# Multiboard_Analog_Connector.net
KiCad netlist of a schematic drawn in Altium Designer
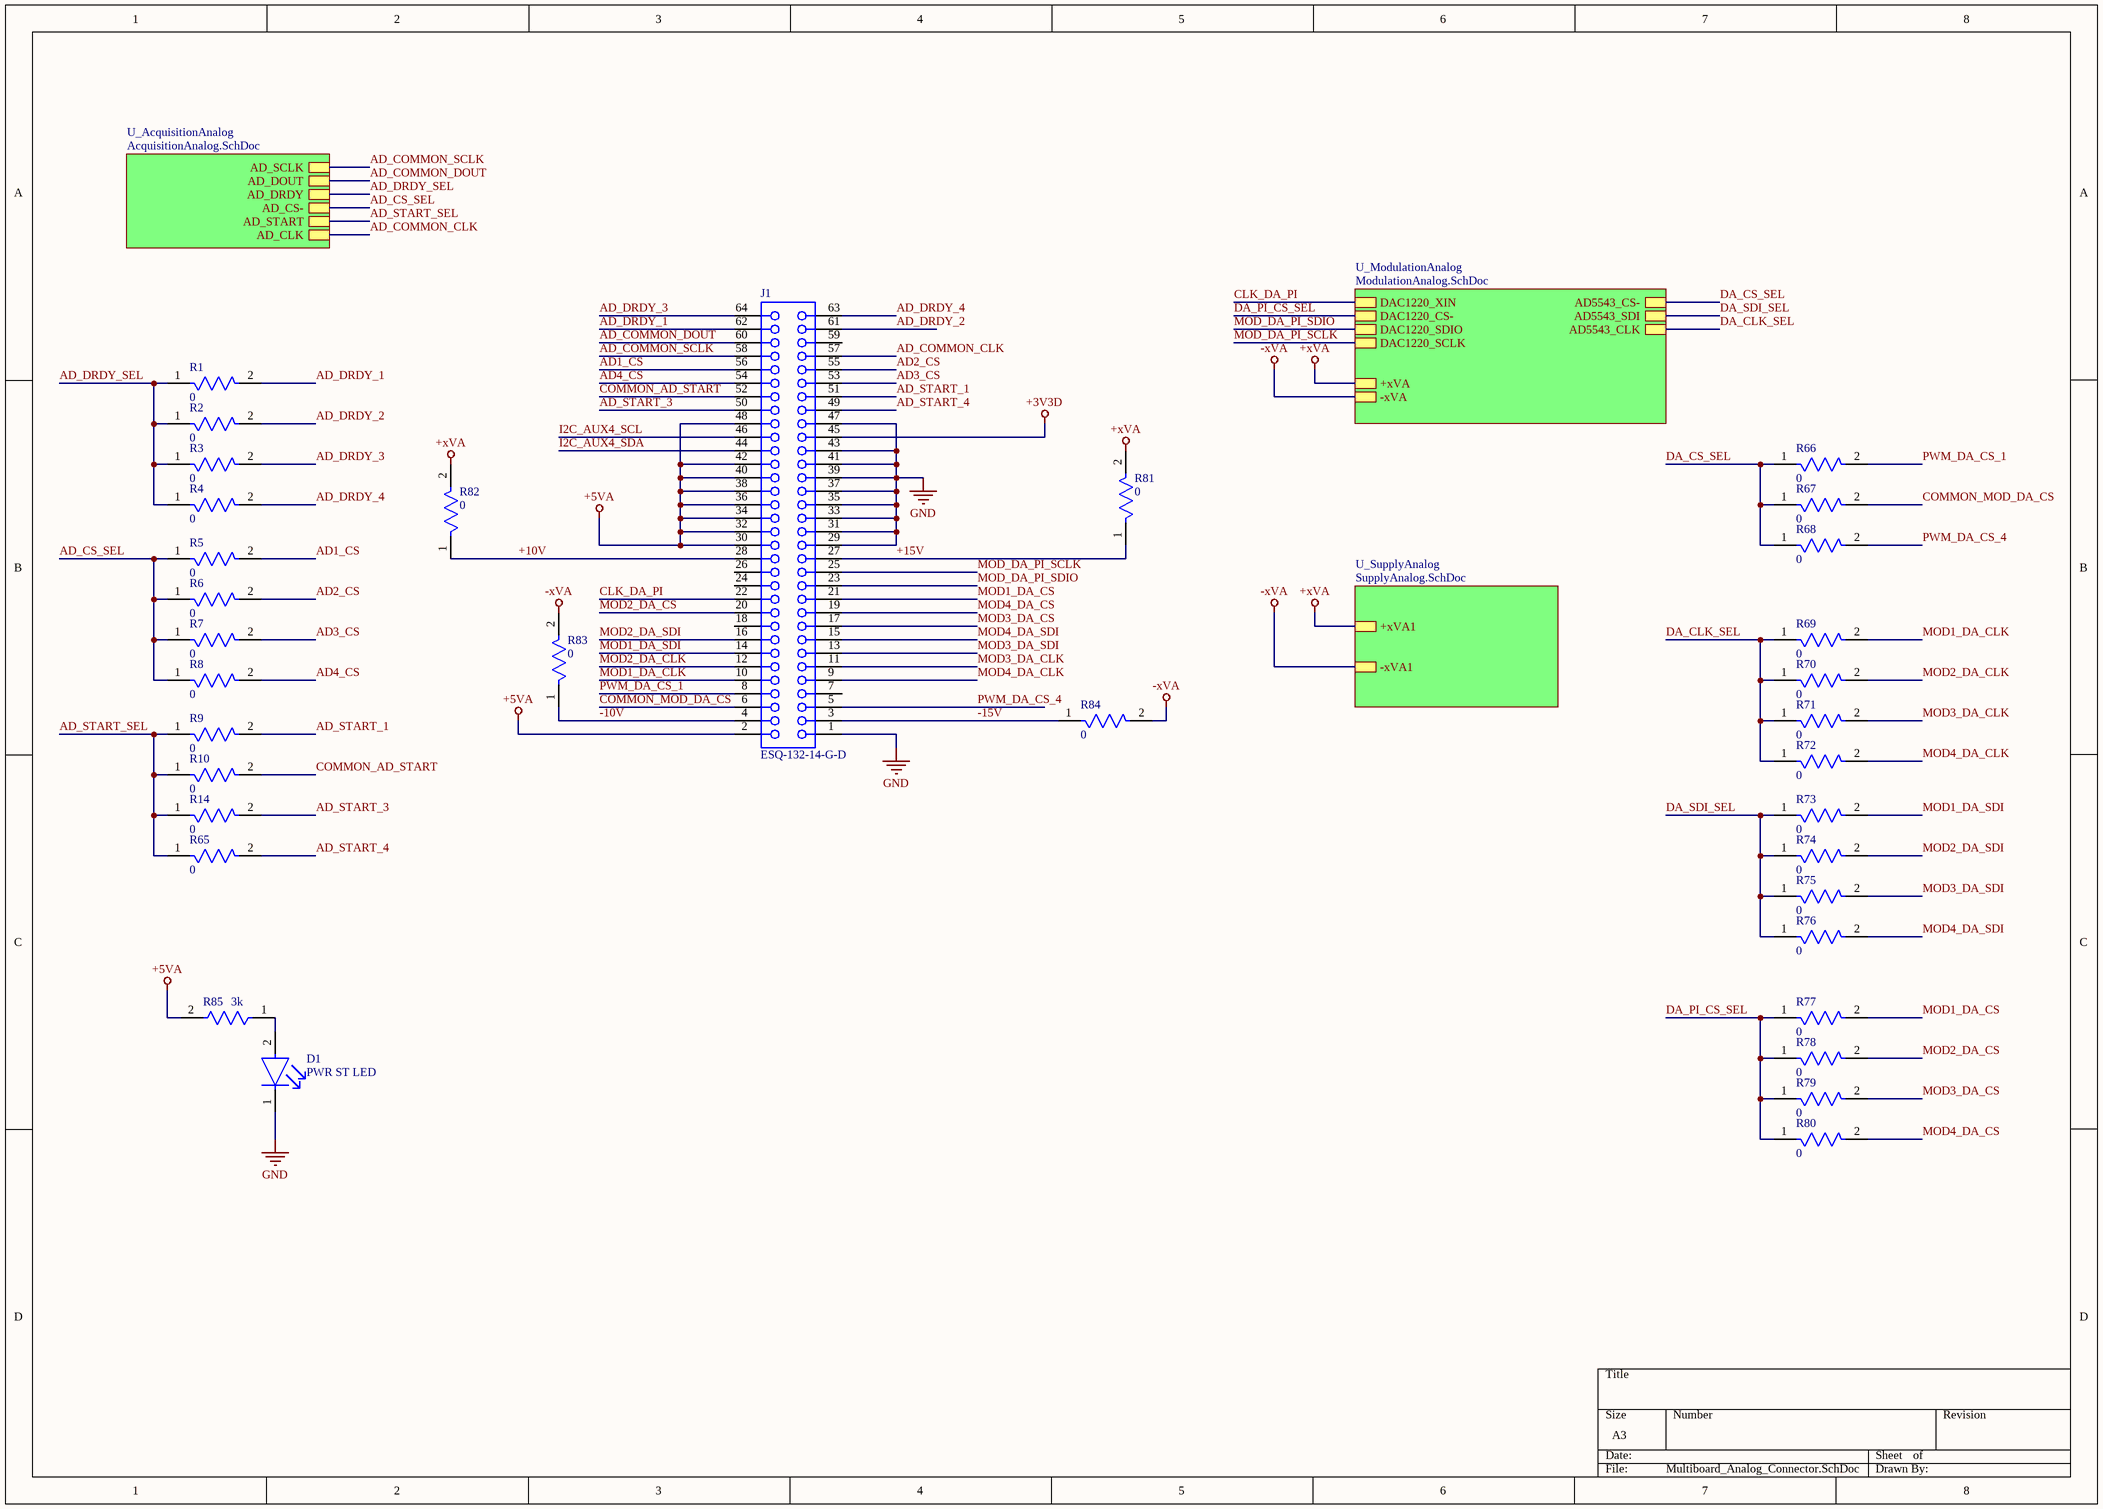
[diagram p0: Multiboard_Analog_Connector.SchDoc]

(export (version "E")
  (design (tool "Eeschema 10.0.6"))
  (components
    (comp (ref "D1")
      (value "PWR ST LED")
      (footprint "FP-APHCM2012SYCK-F01-MFG")
      (description "LED YELLOW CLEAR CHIP SMD")
      (libsource (lib "Altium Content Vault") (part "8706943c75ba83719d021d2fdc84c58"))
    )
    (comp (ref "J1")
      (value "ESQ-132-14-G-D")
      (footprint "SMTC-ESQ-132-14-X-D")
      (fields (field (name "MANUFACTURER") "Samtec"))
      (libsource (lib "Altium Content Vault") (part "SMTC-ESQ-132-14-X-D"))
    )
    (comp (ref "R1")
      (value "0")
      (footprint "FP-RR1220-MFG")
      (description "49.9Ω ±0.5% 0.1W 1/10W Chip Resistor 0805 (2012 Metric) Thin Film")
      (fields (field (name "TOLERANCE") "0.5%"))
      (libsource (lib "Altium Content Vault") (part "1029c3af85768c4190bb7ad29bc67b5"))
    )
    (comp (ref "R2")
      (value "0")
      (footprint "FP-RR1220-MFG")
      (description "49.9Ω ±0.5% 0.1W 1/10W Chip Resistor 0805 (2012 Metric) Thin Film")
      (fields (field (name "TOLERANCE") "0.5%"))
      (libsource (lib "Altium Content Vault") (part "1029c3af85768c4190bb7ad29bc67b5"))
    )
    (comp (ref "R3")
      (value "0")
      (footprint "FP-RR1220-MFG")
      (description "49.9Ω ±0.5% 0.1W 1/10W Chip Resistor 0805 (2012 Metric) Thin Film")
      (fields (field (name "TOLERANCE") "0.5%"))
      (libsource (lib "Altium Content Vault") (part "1029c3af85768c4190bb7ad29bc67b5"))
    )
    (comp (ref "R4")
      (value "0")
      (footprint "FP-RR1220-MFG")
      (description "49.9Ω ±0.5% 0.1W 1/10W Chip Resistor 0805 (2012 Metric) Thin Film")
      (fields (field (name "TOLERANCE") "0.5%"))
      (libsource (lib "Altium Content Vault") (part "1029c3af85768c4190bb7ad29bc67b5"))
    )
    (comp (ref "R5")
      (value "0")
      (footprint "FP-RR1220-MFG")
      (description "49.9Ω ±0.5% 0.1W 1/10W Chip Resistor 0805 (2012 Metric) Thin Film")
      (fields (field (name "TOLERANCE") "0.5%"))
      (libsource (lib "Altium Content Vault") (part "1029c3af85768c4190bb7ad29bc67b5"))
    )
    (comp (ref "R6")
      (value "0")
      (footprint "FP-RR1220-MFG")
      (description "49.9Ω ±0.5% 0.1W 1/10W Chip Resistor 0805 (2012 Metric) Thin Film")
      (fields (field (name "TOLERANCE") "0.5%"))
      (libsource (lib "Altium Content Vault") (part "1029c3af85768c4190bb7ad29bc67b5"))
    )
    (comp (ref "R7")
      (value "0")
      (footprint "FP-RR1220-MFG")
      (description "49.9Ω ±0.5% 0.1W 1/10W Chip Resistor 0805 (2012 Metric) Thin Film")
      (fields (field (name "TOLERANCE") "0.5%"))
      (libsource (lib "Altium Content Vault") (part "1029c3af85768c4190bb7ad29bc67b5"))
    )
    (comp (ref "R8")
      (value "0")
      (footprint "FP-RR1220-MFG")
      (description "49.9Ω ±0.5% 0.1W 1/10W Chip Resistor 0805 (2012 Metric) Thin Film")
      (fields (field (name "TOLERANCE") "0.5%"))
      (libsource (lib "Altium Content Vault") (part "1029c3af85768c4190bb7ad29bc67b5"))
    )
    (comp (ref "R9")
      (value "0")
      (footprint "FP-RR1220-MFG")
      (description "49.9Ω ±0.5% 0.1W 1/10W Chip Resistor 0805 (2012 Metric) Thin Film")
      (fields (field (name "TOLERANCE") "0.5%"))
      (libsource (lib "Altium Content Vault") (part "1029c3af85768c4190bb7ad29bc67b5"))
    )
    (comp (ref "R10")
      (value "0")
      (footprint "FP-RR1220-MFG")
      (description "49.9Ω ±0.5% 0.1W 1/10W Chip Resistor 0805 (2012 Metric) Thin Film")
      (fields (field (name "TOLERANCE") "0.5%"))
      (libsource (lib "Altium Content Vault") (part "1029c3af85768c4190bb7ad29bc67b5"))
    )
    (comp (ref "R14")
      (value "0")
      (footprint "FP-RR1220-MFG")
      (description "49.9Ω ±0.5% 0.1W 1/10W Chip Resistor 0805 (2012 Metric) Thin Film")
      (fields (field (name "TOLERANCE") "0.5%"))
      (libsource (lib "Altium Content Vault") (part "1029c3af85768c4190bb7ad29bc67b5"))
    )
    (comp (ref "R65")
      (value "0")
      (footprint "FP-RR1220-MFG")
      (description "49.9Ω ±0.5% 0.1W 1/10W Chip Resistor 0805 (2012 Metric) Thin Film")
      (fields (field (name "TOLERANCE") "0.5%"))
      (libsource (lib "Altium Content Vault") (part "1029c3af85768c4190bb7ad29bc67b5"))
    )
    (comp (ref "R66")
      (value "0")
      (footprint "FP-RR1220-MFG")
      (description "49.9Ω ±0.5% 0.1W 1/10W Chip Resistor 0805 (2012 Metric) Thin Film")
      (fields (field (name "TOLERANCE") "0.5%"))
      (libsource (lib "Altium Content Vault") (part "1029c3af85768c4190bb7ad29bc67b5"))
    )
    (comp (ref "R67")
      (value "0")
      (footprint "FP-RR1220-MFG")
      (description "49.9Ω ±0.5% 0.1W 1/10W Chip Resistor 0805 (2012 Metric) Thin Film")
      (fields (field (name "TOLERANCE") "0.5%"))
      (libsource (lib "Altium Content Vault") (part "1029c3af85768c4190bb7ad29bc67b5"))
    )
    (comp (ref "R68")
      (value "0")
      (footprint "FP-RR1220-MFG")
      (description "49.9Ω ±0.5% 0.1W 1/10W Chip Resistor 0805 (2012 Metric) Thin Film")
      (fields (field (name "TOLERANCE") "0.5%"))
      (libsource (lib "Altium Content Vault") (part "1029c3af85768c4190bb7ad29bc67b5"))
    )
    (comp (ref "R69")
      (value "0")
      (footprint "FP-RR1220-MFG")
      (description "49.9Ω ±0.5% 0.1W 1/10W Chip Resistor 0805 (2012 Metric) Thin Film")
      (fields (field (name "TOLERANCE") "0.5%"))
      (libsource (lib "Altium Content Vault") (part "1029c3af85768c4190bb7ad29bc67b5"))
    )
    (comp (ref "R70")
      (value "0")
      (footprint "FP-RR1220-MFG")
      (description "49.9Ω ±0.5% 0.1W 1/10W Chip Resistor 0805 (2012 Metric) Thin Film")
      (fields (field (name "TOLERANCE") "0.5%"))
      (libsource (lib "Altium Content Vault") (part "1029c3af85768c4190bb7ad29bc67b5"))
    )
    (comp (ref "R71")
      (value "0")
      (footprint "FP-RR1220-MFG")
      (description "49.9Ω ±0.5% 0.1W 1/10W Chip Resistor 0805 (2012 Metric) Thin Film")
      (fields (field (name "TOLERANCE") "0.5%"))
      (libsource (lib "Altium Content Vault") (part "1029c3af85768c4190bb7ad29bc67b5"))
    )
    (comp (ref "R72")
      (value "0")
      (footprint "FP-RR1220-MFG")
      (description "49.9Ω ±0.5% 0.1W 1/10W Chip Resistor 0805 (2012 Metric) Thin Film")
      (fields (field (name "TOLERANCE") "0.5%"))
      (libsource (lib "Altium Content Vault") (part "1029c3af85768c4190bb7ad29bc67b5"))
    )
    (comp (ref "R73")
      (value "0")
      (footprint "FP-RR1220-MFG")
      (description "49.9Ω ±0.5% 0.1W 1/10W Chip Resistor 0805 (2012 Metric) Thin Film")
      (fields (field (name "TOLERANCE") "0.5%"))
      (libsource (lib "Altium Content Vault") (part "1029c3af85768c4190bb7ad29bc67b5"))
    )
    (comp (ref "R74")
      (value "0")
      (footprint "FP-RR1220-MFG")
      (description "49.9Ω ±0.5% 0.1W 1/10W Chip Resistor 0805 (2012 Metric) Thin Film")
      (fields (field (name "TOLERANCE") "0.5%"))
      (libsource (lib "Altium Content Vault") (part "1029c3af85768c4190bb7ad29bc67b5"))
    )
    (comp (ref "R75")
      (value "0")
      (footprint "FP-RR1220-MFG")
      (description "49.9Ω ±0.5% 0.1W 1/10W Chip Resistor 0805 (2012 Metric) Thin Film")
      (fields (field (name "TOLERANCE") "0.5%"))
      (libsource (lib "Altium Content Vault") (part "1029c3af85768c4190bb7ad29bc67b5"))
    )
    (comp (ref "R76")
      (value "0")
      (footprint "FP-RR1220-MFG")
      (description "49.9Ω ±0.5% 0.1W 1/10W Chip Resistor 0805 (2012 Metric) Thin Film")
      (fields (field (name "TOLERANCE") "0.5%"))
      (libsource (lib "Altium Content Vault") (part "1029c3af85768c4190bb7ad29bc67b5"))
    )
    (comp (ref "R77")
      (value "0")
      (footprint "FP-RR1220-MFG")
      (description "49.9Ω ±0.5% 0.1W 1/10W Chip Resistor 0805 (2012 Metric) Thin Film")
      (fields (field (name "TOLERANCE") "0.5%"))
      (libsource (lib "Altium Content Vault") (part "1029c3af85768c4190bb7ad29bc67b5"))
    )
    (comp (ref "R78")
      (value "0")
      (footprint "FP-RR1220-MFG")
      (description "49.9Ω ±0.5% 0.1W 1/10W Chip Resistor 0805 (2012 Metric) Thin Film")
      (fields (field (name "TOLERANCE") "0.5%"))
      (libsource (lib "Altium Content Vault") (part "1029c3af85768c4190bb7ad29bc67b5"))
    )
    (comp (ref "R79")
      (value "0")
      (footprint "FP-RR1220-MFG")
      (description "49.9Ω ±0.5% 0.1W 1/10W Chip Resistor 0805 (2012 Metric) Thin Film")
      (fields (field (name "TOLERANCE") "0.5%"))
      (libsource (lib "Altium Content Vault") (part "1029c3af85768c4190bb7ad29bc67b5"))
    )
    (comp (ref "R80")
      (value "0")
      (footprint "FP-RR1220-MFG")
      (description "49.9Ω ±0.5% 0.1W 1/10W Chip Resistor 0805 (2012 Metric) Thin Film")
      (fields (field (name "TOLERANCE") "0.5%"))
      (libsource (lib "Altium Content Vault") (part "1029c3af85768c4190bb7ad29bc67b5"))
    )
    (comp (ref "R81")
      (value "0")
      (footprint "FP-RR1220-MFG")
      (description "49.9Ω ±0.5% 0.1W 1/10W Chip Resistor 0805 (2012 Metric) Thin Film")
      (fields (field (name "TOLERANCE") "0.5%"))
      (libsource (lib "Altium Content Vault") (part "1029c3af85768c4190bb7ad29bc67b5"))
    )
    (comp (ref "R82")
      (value "0")
      (footprint "FP-RR1220-MFG")
      (description "49.9Ω ±0.5% 0.1W 1/10W Chip Resistor 0805 (2012 Metric) Thin Film")
      (fields (field (name "TOLERANCE") "0.5%"))
      (libsource (lib "Altium Content Vault") (part "1029c3af85768c4190bb7ad29bc67b5"))
    )
    (comp (ref "R83")
      (value "0")
      (footprint "FP-RR1220-MFG")
      (description "49.9Ω ±0.5% 0.1W 1/10W Chip Resistor 0805 (2012 Metric) Thin Film")
      (fields (field (name "TOLERANCE") "0.5%"))
      (libsource (lib "Altium Content Vault") (part "1029c3af85768c4190bb7ad29bc67b5"))
    )
    (comp (ref "R84")
      (value "0")
      (footprint "FP-RR1220-MFG")
      (description "49.9Ω ±0.5% 0.1W 1/10W Chip Resistor 0805 (2012 Metric) Thin Film")
      (fields (field (name "TOLERANCE") "0.5%"))
      (libsource (lib "Altium Content Vault") (part "1029c3af85768c4190bb7ad29bc67b5"))
    )
    (comp (ref "R85")
      (value "3k")
      (footprint "FP-RR1220-MFG")
      (description "49.9Ω ±0.5% 0.1W 1/10W Chip Resistor 0805 (2012 Metric) Thin Film")
      (fields (field (name "TOLERANCE") "0.5%"))
      (libsource (lib "Altium Content Vault") (part "1029c3af85768c4190bb7ad29bc67b5"))
    )
  )
  (nets
    (net (code "1") (name "+3V3D") (class "Default")
      (node (ref "J1") (pin "45") (pinfunction "45_45") (pintype "passive"))
    )
    (net (code "2") (name "+5VA") (class "Default")
      (node (ref "J1") (pin "2") (pinfunction "2_2") (pintype "passive"))
      (node (ref "J1") (pin "30") (pinfunction "30_30") (pintype "passive"))
      (node (ref "J1") (pin "32") (pinfunction "32_32") (pintype "passive"))
      (node (ref "J1") (pin "34") (pinfunction "34_34") (pintype "passive"))
      (node (ref "J1") (pin "36") (pinfunction "36_36") (pintype "passive"))
      (node (ref "J1") (pin "38") (pinfunction "38_38") (pintype "passive"))
      (node (ref "J1") (pin "40") (pinfunction "40_40") (pintype "passive"))
      (node (ref "J1") (pin "42") (pinfunction "42_42") (pintype "passive"))
      (node (ref "J1") (pin "48") (pinfunction "48_48") (pintype "passive"))
      (node (ref "R85") (pin "2") (pinfunction "2_2") (pintype "passive"))
    )
    (net (code "3") (name "+xVA") (class "Default")
      (node (ref "R81") (pin "2") (pinfunction "2_2") (pintype "passive"))
      (node (ref "R82") (pin "2") (pinfunction "2_2") (pintype "passive"))
    )
    (net (code "4") (name "-xVA") (class "Default")
      (node (ref "R83") (pin "2") (pinfunction "2_2") (pintype "passive"))
      (node (ref "R84") (pin "2") (pinfunction "2_2") (pintype "passive"))
    )
    (net (code "5") (name "/+10V") (class "Default")
      (node (ref "J1") (pin "28") (pinfunction "28_28") (pintype "passive"))
      (node (ref "R82") (pin "1") (pinfunction "1_1") (pintype "passive"))
    )
    (net (code "6") (name "/+15V") (class "Default")
      (node (ref "J1") (pin "27") (pinfunction "27_27") (pintype "passive"))
      (node (ref "R81") (pin "1") (pinfunction "1_1") (pintype "passive"))
    )
    (net (code "7") (name "/-10V") (class "Default")
      (node (ref "J1") (pin "4") (pinfunction "4_4") (pintype "passive"))
      (node (ref "R83") (pin "1") (pinfunction "1_1") (pintype "passive"))
    )
    (net (code "8") (name "/-15V") (class "Default")
      (node (ref "J1") (pin "3") (pinfunction "3_3") (pintype "passive"))
      (node (ref "R84") (pin "1") (pinfunction "1_1") (pintype "passive"))
    )
    (net (code "9") (name "/AD1_CS") (class "Default")
      (node (ref "J1") (pin "56") (pinfunction "56_56") (pintype "passive"))
      (node (ref "R5") (pin "2") (pinfunction "2_2") (pintype "passive"))
    )
    (net (code "10") (name "/AD2_CS") (class "Default")
      (node (ref "J1") (pin "55") (pinfunction "55_55") (pintype "passive"))
      (node (ref "R6") (pin "2") (pinfunction "2_2") (pintype "passive"))
    )
    (net (code "11") (name "/AD3_CS") (class "Default")
      (node (ref "J1") (pin "53") (pinfunction "53_53") (pintype "passive"))
      (node (ref "R7") (pin "2") (pinfunction "2_2") (pintype "passive"))
    )
    (net (code "12") (name "/AD4_CS") (class "Default")
      (node (ref "J1") (pin "54") (pinfunction "54_54") (pintype "passive"))
      (node (ref "R8") (pin "2") (pinfunction "2_2") (pintype "passive"))
    )
    (net (code "13") (name "/AD_COMMON_CLK") (class "Default")
      (node (ref "J1") (pin "57") (pinfunction "57_57") (pintype "passive"))
    )
    (net (code "14") (name "/AD_COMMON_DOUT") (class "Default")
      (node (ref "J1") (pin "60") (pinfunction "60_60") (pintype "passive"))
    )
    (net (code "15") (name "/AD_COMMON_SCLK") (class "Default")
      (node (ref "J1") (pin "58") (pinfunction "58_58") (pintype "passive"))
    )
    (net (code "16") (name "/AD_CS_SEL") (class "Default")
      (node (ref "R5") (pin "1") (pinfunction "1_1") (pintype "passive"))
      (node (ref "R6") (pin "1") (pinfunction "1_1") (pintype "passive"))
      (node (ref "R7") (pin "1") (pinfunction "1_1") (pintype "passive"))
      (node (ref "R8") (pin "1") (pinfunction "1_1") (pintype "passive"))
    )
    (net (code "17") (name "/AD_DRDY_1") (class "Default")
      (node (ref "J1") (pin "62") (pinfunction "62_62") (pintype "passive"))
      (node (ref "R1") (pin "2") (pinfunction "2_2") (pintype "passive"))
    )
    (net (code "18") (name "/AD_DRDY_2") (class "Default")
      (node (ref "J1") (pin "61") (pinfunction "61_61") (pintype "passive"))
      (node (ref "R2") (pin "2") (pinfunction "2_2") (pintype "passive"))
    )
    (net (code "19") (name "/AD_DRDY_3") (class "Default")
      (node (ref "J1") (pin "64") (pinfunction "64_64") (pintype "passive"))
      (node (ref "R3") (pin "2") (pinfunction "2_2") (pintype "passive"))
    )
    (net (code "20") (name "/AD_DRDY_4") (class "Default")
      (node (ref "J1") (pin "63") (pinfunction "63_63") (pintype "passive"))
      (node (ref "R4") (pin "2") (pinfunction "2_2") (pintype "passive"))
    )
    (net (code "21") (name "/AD_DRDY_SEL") (class "Default")
      (node (ref "R1") (pin "1") (pinfunction "1_1") (pintype "passive"))
      (node (ref "R2") (pin "1") (pinfunction "1_1") (pintype "passive"))
      (node (ref "R3") (pin "1") (pinfunction "1_1") (pintype "passive"))
      (node (ref "R4") (pin "1") (pinfunction "1_1") (pintype "passive"))
    )
    (net (code "22") (name "/AD_START_1") (class "Default")
      (node (ref "J1") (pin "51") (pinfunction "51_51") (pintype "passive"))
      (node (ref "R9") (pin "2") (pinfunction "2_2") (pintype "passive"))
    )
    (net (code "23") (name "/AD_START_3") (class "Default")
      (node (ref "J1") (pin "50") (pinfunction "50_50") (pintype "passive"))
      (node (ref "R14") (pin "2") (pinfunction "2_2") (pintype "passive"))
    )
    (net (code "24") (name "/AD_START_4") (class "Default")
      (node (ref "J1") (pin "49") (pinfunction "49_49") (pintype "passive"))
      (node (ref "R65") (pin "2") (pinfunction "2_2") (pintype "passive"))
    )
    (net (code "25") (name "/AD_START_SEL") (class "Default")
      (node (ref "R10") (pin "1") (pinfunction "1_1") (pintype "passive"))
      (node (ref "R14") (pin "1") (pinfunction "1_1") (pintype "passive"))
      (node (ref "R65") (pin "1") (pinfunction "1_1") (pintype "passive"))
      (node (ref "R9") (pin "1") (pinfunction "1_1") (pintype "passive"))
    )
    (net (code "26") (name "/CLK_DA_PI") (class "Default")
      (node (ref "J1") (pin "22") (pinfunction "22_22") (pintype "passive"))
    )
    (net (code "27") (name "/COMMON_AD_START") (class "Default")
      (node (ref "J1") (pin "52") (pinfunction "52_52") (pintype "passive"))
      (node (ref "R10") (pin "2") (pinfunction "2_2") (pintype "passive"))
    )
    (net (code "28") (name "/COMMON_MOD_DA_CS") (class "Default")
      (node (ref "J1") (pin "6") (pinfunction "6_6") (pintype "passive"))
      (node (ref "R67") (pin "2") (pinfunction "2_2") (pintype "passive"))
    )
    (net (code "29") (name "/DA_CLK_SEL") (class "Default")
      (node (ref "R69") (pin "1") (pinfunction "1_1") (pintype "passive"))
      (node (ref "R70") (pin "1") (pinfunction "1_1") (pintype "passive"))
      (node (ref "R71") (pin "1") (pinfunction "1_1") (pintype "passive"))
      (node (ref "R72") (pin "1") (pinfunction "1_1") (pintype "passive"))
    )
    (net (code "30") (name "/DA_CS_SEL") (class "Default")
      (node (ref "R66") (pin "1") (pinfunction "1_1") (pintype "passive"))
      (node (ref "R67") (pin "1") (pinfunction "1_1") (pintype "passive"))
      (node (ref "R68") (pin "1") (pinfunction "1_1") (pintype "passive"))
    )
    (net (code "31") (name "/DA_PI_CS_SEL") (class "Default")
      (node (ref "R77") (pin "1") (pinfunction "1_1") (pintype "passive"))
      (node (ref "R78") (pin "1") (pinfunction "1_1") (pintype "passive"))
      (node (ref "R79") (pin "1") (pinfunction "1_1") (pintype "passive"))
      (node (ref "R80") (pin "1") (pinfunction "1_1") (pintype "passive"))
    )
    (net (code "32") (name "/DA_SDI_SEL") (class "Default")
      (node (ref "R73") (pin "1") (pinfunction "1_1") (pintype "passive"))
      (node (ref "R74") (pin "1") (pinfunction "1_1") (pintype "passive"))
      (node (ref "R75") (pin "1") (pinfunction "1_1") (pintype "passive"))
      (node (ref "R76") (pin "1") (pinfunction "1_1") (pintype "passive"))
    )
    (net (code "33") (name "/I2C_AUX4_SCL") (class "Default")
      (node (ref "J1") (pin "46") (pinfunction "46_46") (pintype "passive"))
    )
    (net (code "34") (name "/I2C_AUX4_SDA") (class "Default")
      (node (ref "J1") (pin "44") (pinfunction "44_44") (pintype "passive"))
    )
    (net (code "35") (name "/MOD1_DA_CLK") (class "Default")
      (node (ref "J1") (pin "10") (pinfunction "10_10") (pintype "passive"))
      (node (ref "R69") (pin "2") (pinfunction "2_2") (pintype "passive"))
    )
    (net (code "36") (name "/MOD1_DA_CS") (class "Default")
      (node (ref "J1") (pin "21") (pinfunction "21_21") (pintype "passive"))
      (node (ref "R77") (pin "2") (pinfunction "2_2") (pintype "passive"))
    )
    (net (code "37") (name "/MOD1_DA_SDI") (class "Default")
      (node (ref "J1") (pin "14") (pinfunction "14_14") (pintype "passive"))
      (node (ref "R73") (pin "2") (pinfunction "2_2") (pintype "passive"))
    )
    (net (code "38") (name "/MOD2_DA_CLK") (class "Default")
      (node (ref "J1") (pin "12") (pinfunction "12_12") (pintype "passive"))
      (node (ref "R70") (pin "2") (pinfunction "2_2") (pintype "passive"))
    )
    (net (code "39") (name "/MOD2_DA_CS") (class "Default")
      (node (ref "J1") (pin "20") (pinfunction "20_20") (pintype "passive"))
      (node (ref "R78") (pin "2") (pinfunction "2_2") (pintype "passive"))
    )
    (net (code "40") (name "/MOD2_DA_SDI") (class "Default")
      (node (ref "J1") (pin "16") (pinfunction "16_16") (pintype "passive"))
      (node (ref "R74") (pin "2") (pinfunction "2_2") (pintype "passive"))
    )
    (net (code "41") (name "/MOD3_DA_CLK") (class "Default")
      (node (ref "J1") (pin "11") (pinfunction "11_11") (pintype "passive"))
      (node (ref "R71") (pin "2") (pinfunction "2_2") (pintype "passive"))
    )
    (net (code "42") (name "/MOD3_DA_CS") (class "Default")
      (node (ref "J1") (pin "17") (pinfunction "17_17") (pintype "passive"))
      (node (ref "R79") (pin "2") (pinfunction "2_2") (pintype "passive"))
    )
    (net (code "43") (name "/MOD3_DA_SDI") (class "Default")
      (node (ref "J1") (pin "13") (pinfunction "13_13") (pintype "passive"))
      (node (ref "R75") (pin "2") (pinfunction "2_2") (pintype "passive"))
    )
    (net (code "44") (name "/MOD4_DA_CLK") (class "Default")
      (node (ref "J1") (pin "9") (pinfunction "9_9") (pintype "passive"))
      (node (ref "R72") (pin "2") (pinfunction "2_2") (pintype "passive"))
    )
    (net (code "45") (name "/MOD4_DA_CS") (class "Default")
      (node (ref "J1") (pin "19") (pinfunction "19_19") (pintype "passive"))
      (node (ref "R80") (pin "2") (pinfunction "2_2") (pintype "passive"))
    )
    (net (code "46") (name "/MOD4_DA_SDI") (class "Default")
      (node (ref "J1") (pin "15") (pinfunction "15_15") (pintype "passive"))
      (node (ref "R76") (pin "2") (pinfunction "2_2") (pintype "passive"))
    )
    (net (code "47") (name "/MOD_DA_PI_SCLK") (class "Default")
      (node (ref "J1") (pin "25") (pinfunction "25_25") (pintype "passive"))
    )
    (net (code "48") (name "/MOD_DA_PI_SDIO") (class "Default")
      (node (ref "J1") (pin "23") (pinfunction "23_23") (pintype "passive"))
    )
    (net (code "49") (name "/PWM_DA_CS_1") (class "Default")
      (node (ref "J1") (pin "8") (pinfunction "8_8") (pintype "passive"))
      (node (ref "R66") (pin "2") (pinfunction "2_2") (pintype "passive"))
    )
    (net (code "50") (name "/PWM_DA_CS_4") (class "Default")
      (node (ref "J1") (pin "5") (pinfunction "5_5") (pintype "passive"))
      (node (ref "R68") (pin "2") (pinfunction "2_2") (pintype "passive"))
    )
    (net (code "51") (name "GND") (class "Default")
      (node (ref "D1") (pin "1") (pinfunction "C_1") (pintype "passive"))
      (node (ref "J1") (pin "1") (pinfunction "1_1") (pintype "passive"))
      (node (ref "J1") (pin "29") (pinfunction "29_29") (pintype "passive"))
      (node (ref "J1") (pin "31") (pinfunction "31_31") (pintype "passive"))
      (node (ref "J1") (pin "33") (pinfunction "33_33") (pintype "passive"))
      (node (ref "J1") (pin "35") (pinfunction "35_35") (pintype "passive"))
      (node (ref "J1") (pin "37") (pinfunction "37_37") (pintype "passive"))
      (node (ref "J1") (pin "39") (pinfunction "39_39") (pintype "passive"))
      (node (ref "J1") (pin "41") (pinfunction "41_41") (pintype "passive"))
      (node (ref "J1") (pin "43") (pinfunction "43_43") (pintype "passive"))
      (node (ref "J1") (pin "47") (pinfunction "47_47") (pintype "passive"))
    )
    (net (code "52") (name "Net-(D1-A)") (class "Default")
      (node (ref "D1") (pin "2") (pinfunction "A_2") (pintype "passive"))
      (node (ref "R85") (pin "1") (pinfunction "1_1") (pintype "passive"))
    )
    (net (code "53") (name "unconnected-(J1-Pad7)") (class "Default")
      (node (ref "J1") (pin "7") (pinfunction "7_7") (pintype "passive"))
    )
    (net (code "54") (name "unconnected-(J1-Pad18)") (class "Default")
      (node (ref "J1") (pin "18") (pinfunction "18_18") (pintype "passive"))
    )
    (net (code "55") (name "unconnected-(J1-Pad24)") (class "Default")
      (node (ref "J1") (pin "24") (pinfunction "24_24") (pintype "passive"))
    )
    (net (code "56") (name "unconnected-(J1-Pad26)") (class "Default")
      (node (ref "J1") (pin "26") (pinfunction "26_26") (pintype "passive"))
    )
    (net (code "57") (name "unconnected-(J1-Pad59)") (class "Default")
      (node (ref "J1") (pin "59") (pinfunction "59_59") (pintype "passive"))
    )
  )
)
